# AdapterBoardv0_2.net
KiCad netlist of a schematic drawn in EAGLE
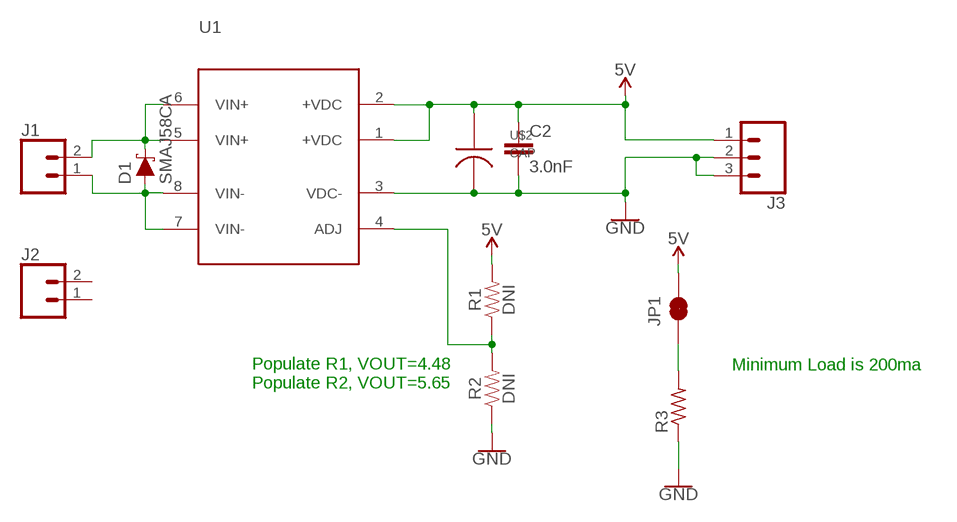
[diagram p0: schematic, sheet 1]

(export (version "E")
  (design (tool "Eeschema 10.0.6"))
  (components
    (comp (ref "C2")
      (value "3.0nF")
      (footprint "eagle-import:0603")
      (libsource (lib "eagle-import") (part "3.0NF-0603-50V-5%"))
    )
    (comp (ref "D1")
      (value "SMAJ58CA")
      (footprint "eagle-import:SMA-DIODE")
      (libsource (lib "eagle-import") (part "DIODE-SCHOTTKY-B340A"))
    )
    (comp (ref "J1")
      (value "CONN_02")
      (footprint "eagle-import:1X02")
      (libsource (lib "eagle-import") (part "CONN_02"))
    )
    (comp (ref "J2")
      (value "CONN_02")
      (footprint "eagle-import:1X02")
      (libsource (lib "eagle-import") (part "CONN_02"))
    )
    (comp (ref "J3")
      (value "CONN_03")
      (footprint "eagle-import:1X03")
      (libsource (lib "eagle-import") (part "CONN_03"))
    )
    (comp (ref "JP1")
      (value "JUMPER-SMT_2_NC_TRACE_NO-SILK")
      (footprint "eagle-import:SMT-JUMPER_2_NC_TRACE_NO-SILK")
      (libsource (lib "eagle-import") (part "JUMPER-SMT_2_NC_TRACE_NO-SILK"))
    )
    (comp (ref "R1")
      (value "DNI")
      (footprint "eagle-import:0603")
      (libsource (lib "eagle-import") (part "0.05OHM-0603-1/5W-1%"))
    )
    (comp (ref "R2")
      (value "DNI")
      (footprint "eagle-import:0603")
      (libsource (lib "eagle-import") (part "0.05OHM-0603-1/5W-1%"))
    )
    (comp (ref "R3")
      (value "R-US_R1210")
      (footprint "eagle-import:R1210")
      (libsource (lib "eagle-import") (part "R-US_R1210"))
    )
    (comp (ref "U$2")
      (value "CAP")
      (footprint "eagle-import:CAP")
      (libsource (lib "eagle-import") (part "CAP"))
    )
    (comp (ref "U1")
      (value "PARTICLE_AG9800AG99")
      (footprint "eagle-import:AG9900")
      (libsource (lib "eagle-import") (part "PARTICLE_AG9800AG99"))
    )
  )
  (nets
    (net (code "1") (name "5V") (class "Default")
      (node (ref "C2") (pin "1") (pinfunction "1_1") (pintype "passive"))
      (node (ref "J3") (pin "1") (pinfunction "1_1") (pintype "passive"))
      (node (ref "JP1") (pin "2") (pinfunction "2_2") (pintype "passive"))
      (node (ref "R1") (pin "2") (pinfunction "2_2") (pintype "passive"))
      (node (ref "U$2") (pin "A") (pinfunction "P$1_A") (pintype "bidirectional"))
      (node (ref "U1") (pin "1") (pinfunction "+VDC_1") (pintype "bidirectional"))
      (node (ref "U1") (pin "2") (pinfunction "+VDC_2") (pintype "bidirectional"))
    )
    (net (code "2") (name "GND") (class "Default")
      (node (ref "C2") (pin "2") (pinfunction "2_2") (pintype "passive"))
      (node (ref "J3") (pin "2") (pinfunction "2_2") (pintype "passive"))
      (node (ref "J3") (pin "3") (pinfunction "3_3") (pintype "passive"))
      (node (ref "R2") (pin "1") (pinfunction "1_1") (pintype "passive"))
      (node (ref "R3") (pin "1") (pinfunction "1_1") (pintype "passive"))
      (node (ref "U$2") (pin "C") (pinfunction "P$2_C") (pintype "bidirectional"))
      (node (ref "U1") (pin "3") (pinfunction "VDC-_3") (pintype "bidirectional"))
    )
    (net (code "3") (name "Net-(D1-PadA)") (class "Default")
      (node (ref "D1") (pin "A") (pinfunction "A_A") (pintype "passive"))
      (node (ref "J1") (pin "1") (pinfunction "1_1") (pintype "passive"))
      (node (ref "U1") (pin "7") (pinfunction "VIN-_7") (pintype "bidirectional"))
      (node (ref "U1") (pin "8") (pinfunction "VIN-_8") (pintype "bidirectional"))
    )
    (net (code "4") (name "Net-(D1-PadC)") (class "Default")
      (node (ref "D1") (pin "C") (pinfunction "C_C") (pintype "passive"))
      (node (ref "J1") (pin "2") (pinfunction "2_2") (pintype "passive"))
      (node (ref "U1") (pin "5") (pinfunction "VIN+_5") (pintype "bidirectional"))
      (node (ref "U1") (pin "6") (pinfunction "VIN+_6") (pintype "bidirectional"))
    )
    (net (code "5") (name "Net-(JP1-Pad1)") (class "Default")
      (node (ref "JP1") (pin "1") (pinfunction "1_1") (pintype "passive"))
      (node (ref "R3") (pin "2") (pinfunction "2_2") (pintype "passive"))
    )
    (net (code "6") (name "Net-(U1-ADJ)") (class "Default")
      (node (ref "R1") (pin "1") (pinfunction "1_1") (pintype "passive"))
      (node (ref "R2") (pin "2") (pinfunction "2_2") (pintype "passive"))
      (node (ref "U1") (pin "4") (pinfunction "ADJ_4") (pintype "bidirectional"))
    )
    (net (code "7") (name "unconnected-(J2-Pad1)") (class "Default")
      (node (ref "J2") (pin "1") (pinfunction "1_1") (pintype "passive"))
    )
    (net (code "8") (name "unconnected-(J2-Pad2)") (class "Default")
      (node (ref "J2") (pin "2") (pinfunction "2_2") (pintype "passive"))
    )
  )
)
